# bln-001.net
KiCad netlist of a schematic drawn in EAGLE
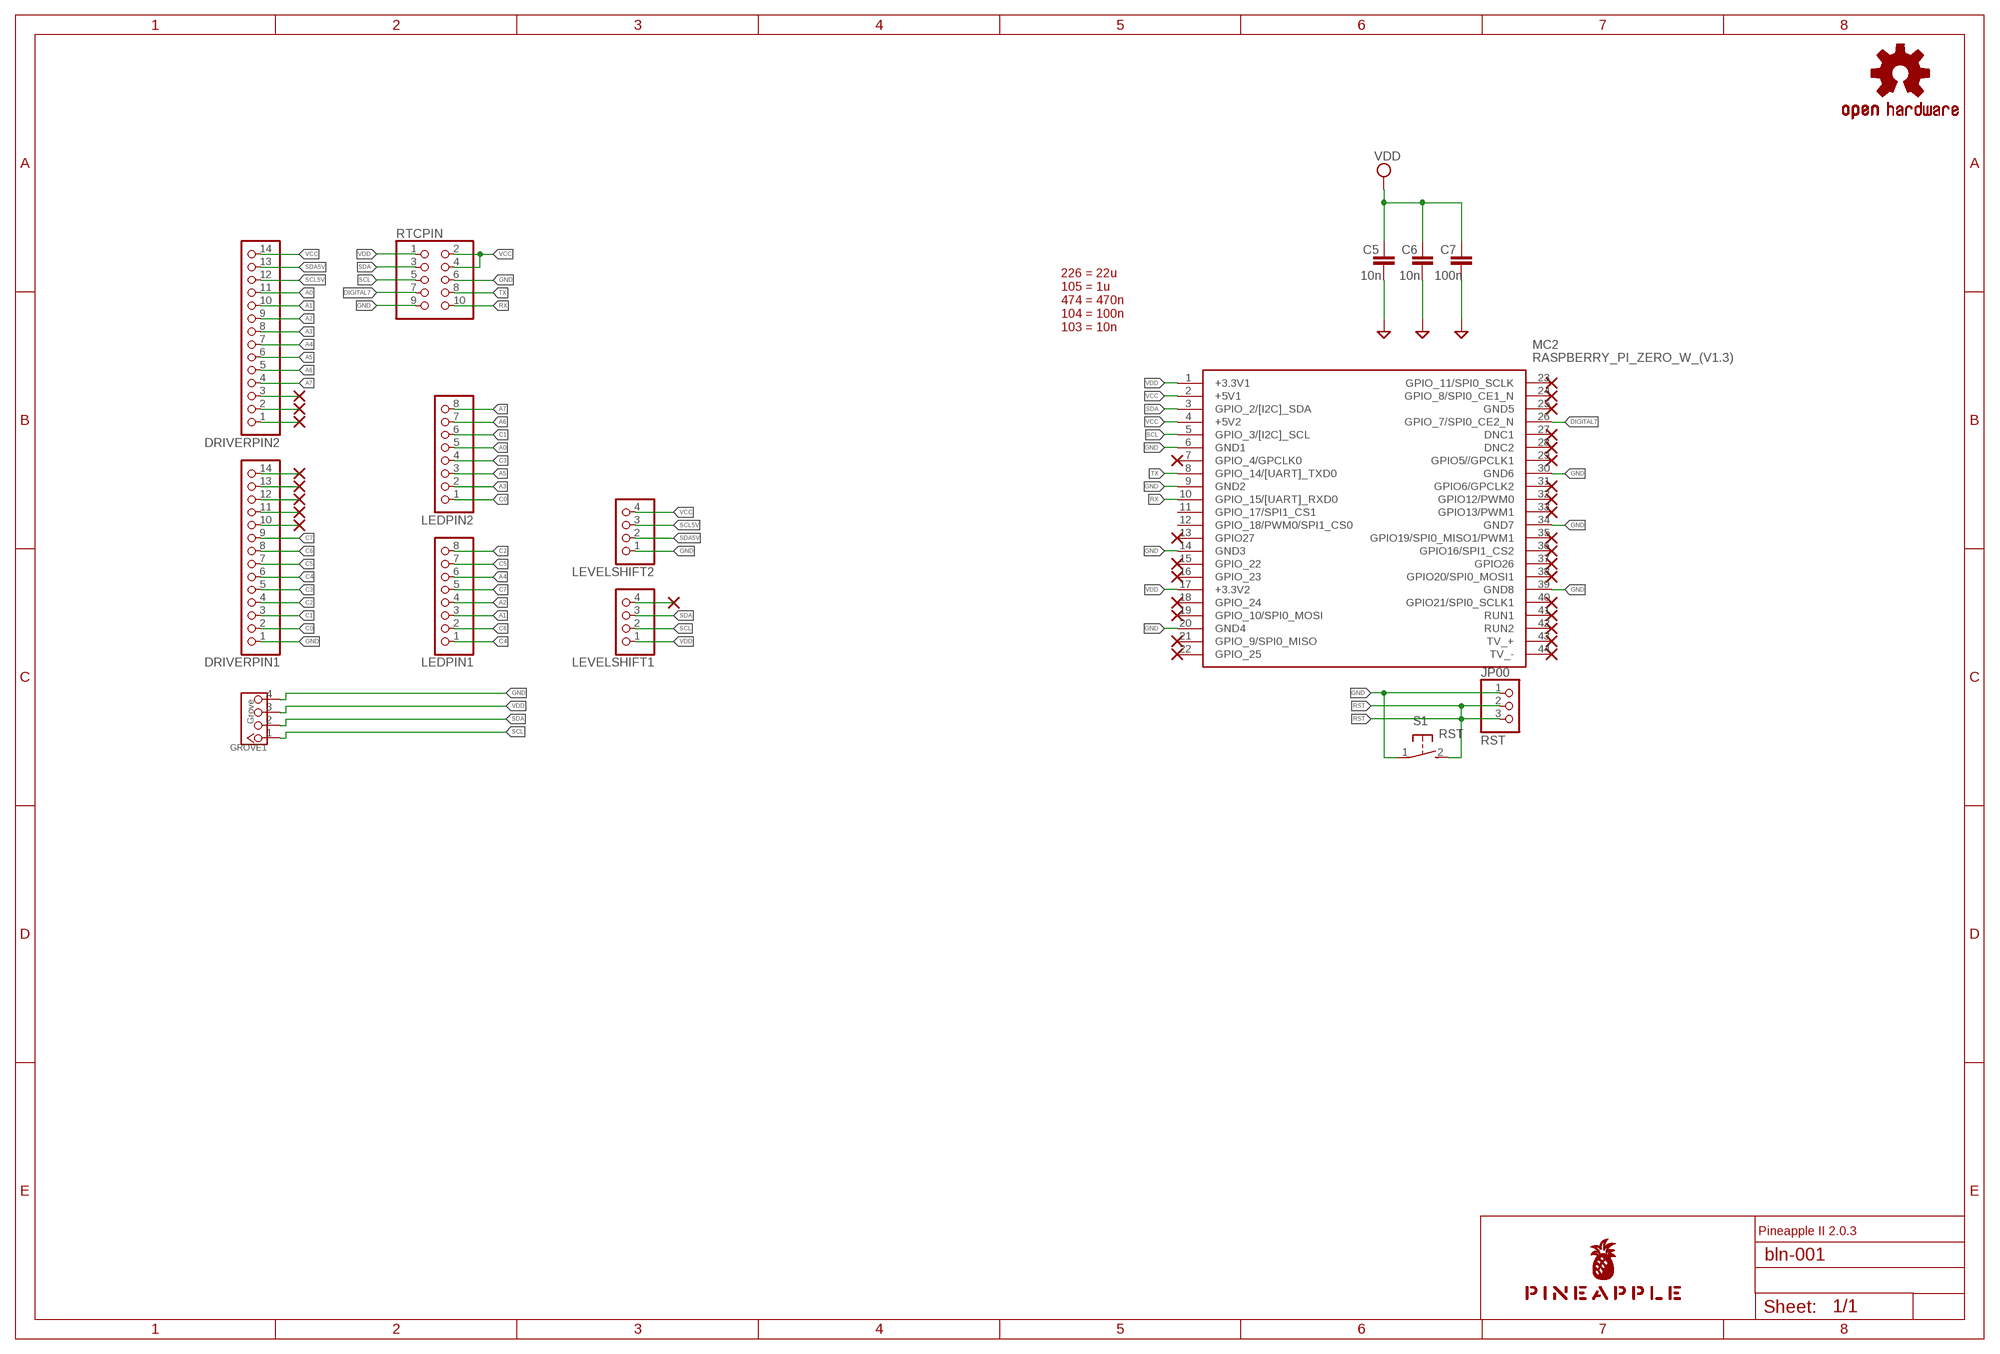
[diagram p0: schematic, sheet 1]

(export (version "E")
  (design (tool "Eeschema 10.0.6"))
  (components
    (comp (ref "C5")
      (value "10n")
      (footprint "eagle-import:C025-024X044")
      (libsource (lib "eagle-import") (part "C-EU025-024X044"))
    )
    (comp (ref "C6")
      (value "10n")
      (footprint "eagle-import:C025-024X044")
      (libsource (lib "eagle-import") (part "C-EU025-024X044"))
    )
    (comp (ref "C7")
      (value "100n")
      (footprint "eagle-import:C025-024X044")
      (libsource (lib "eagle-import") (part "C-EU025-024X044"))
    )
    (comp (ref "DRIVERPIN1")
      (value "PINHD-1X14")
      (footprint "eagle-import:1X14")
      (libsource (lib "eagle-import") (part "PINHD-1X14"))
    )
    (comp (ref "DRIVERPIN2")
      (value "PINHD-1X14")
      (footprint "eagle-import:1X14")
      (libsource (lib "eagle-import") (part "PINHD-1X14"))
    )
    (comp (ref "GROVE1")
      (value "Grove")
      (footprint "eagle-import:4P-2.0-90D")
      (libsource (lib "eagle-import") (part "TWIG-4P-2.0'90D'"))
    )
    (comp (ref "JP00")
      (value "RST")
      (footprint "eagle-import:1X03")
      (libsource (lib "eagle-import") (part "PINHD-1X3"))
    )
    (comp (ref "LEDPIN1")
      (value "PINHD-1X8BIG")
      (footprint "eagle-import:1X08-BIG")
      (libsource (lib "eagle-import") (part "PINHD-1X8BIG"))
    )
    (comp (ref "LEDPIN2")
      (value "PINHD-1X8BIG")
      (footprint "eagle-import:1X08-BIG")
      (libsource (lib "eagle-import") (part "PINHD-1X8BIG"))
    )
    (comp (ref "LEVELSHIFT1")
      (value "PINHD-1X4")
      (footprint "eagle-import:1X04")
      (libsource (lib "eagle-import") (part "PINHD-1X4"))
    )
    (comp (ref "LEVELSHIFT2")
      (value "PINHD-1X4")
      (footprint "eagle-import:1X04")
      (libsource (lib "eagle-import") (part "PINHD-1X4"))
    )
    (comp (ref "LOGO1")
      (value "OSHW-LOGOS-COPPER")
      (footprint "eagle-import:OSHW-LOGO-S_COPPER")
      (libsource (lib "eagle-import") (part "OSHW-LOGOS-COPPER"))
    )
    (comp (ref "MC2")
      (value "RASPBERRY_PI_ZERO_W_(V1.3)")
      (footprint "eagle-import:RASPBERRYPIZEROWV13")
      (fields (field (name "ARROW_PART_NUMBER") "Raspberry Pi Zero W (v1.3)"))
      (libsource (lib "eagle-import") (part "RASPBERRY_PI_ZERO_W_(V1.3)"))
    )
    (comp (ref "RTCPIN")
      (value "PINHD-2X5")
      (footprint "eagle-import:2X05")
      (libsource (lib "eagle-import") (part "PINHD-2X5"))
    )
    (comp (ref "S1")
      (value "RST")
      (footprint "eagle-import:B3F-31XX")
      (fields (field (name "MPN") "B3F-3100"))
      (libsource (lib "eagle-import") (part "31-XX"))
    )
    (comp (ref "U$1")
      (value "PINEAPPLE450_SILK")
      (footprint "eagle-import:PINEAPPLE450_SILK")
      (libsource (lib "eagle-import") (part "PINEAPPLE450_SILK"))
    )
  )
  (nets
    (net (code "1") (name "A0") (class "Default")
      (node (ref "DRIVERPIN2") (pin "11") (pinfunction "11_11") (pintype "passive"))
      (node (ref "LEDPIN2") (pin "5") (pinfunction "5_5") (pintype "passive"))
    )
    (net (code "2") (name "A1") (class "Default")
      (node (ref "DRIVERPIN2") (pin "10") (pinfunction "10_10") (pintype "passive"))
      (node (ref "LEDPIN1") (pin "3") (pinfunction "3_3") (pintype "passive"))
    )
    (net (code "3") (name "A2") (class "Default")
      (node (ref "DRIVERPIN2") (pin "9") (pinfunction "9_9") (pintype "passive"))
      (node (ref "LEDPIN1") (pin "4") (pinfunction "4_4") (pintype "passive"))
    )
    (net (code "4") (name "A3") (class "Default")
      (node (ref "DRIVERPIN2") (pin "8") (pinfunction "8_8") (pintype "passive"))
      (node (ref "LEDPIN2") (pin "2") (pinfunction "2_2") (pintype "passive"))
    )
    (net (code "5") (name "A4") (class "Default")
      (node (ref "DRIVERPIN2") (pin "7") (pinfunction "7_7") (pintype "passive"))
      (node (ref "LEDPIN1") (pin "6") (pinfunction "6_6") (pintype "passive"))
    )
    (net (code "6") (name "A5") (class "Default")
      (node (ref "DRIVERPIN2") (pin "6") (pinfunction "6_6") (pintype "passive"))
      (node (ref "LEDPIN2") (pin "3") (pinfunction "3_3") (pintype "passive"))
    )
    (net (code "7") (name "A6") (class "Default")
      (node (ref "DRIVERPIN2") (pin "5") (pinfunction "5_5") (pintype "passive"))
      (node (ref "LEDPIN2") (pin "7") (pinfunction "7_7") (pintype "passive"))
    )
    (net (code "8") (name "A7") (class "Default")
      (node (ref "DRIVERPIN2") (pin "4") (pinfunction "4_4") (pintype "passive"))
      (node (ref "LEDPIN2") (pin "8") (pinfunction "8_8") (pintype "passive"))
    )
    (net (code "9") (name "C0") (class "Default")
      (node (ref "DRIVERPIN1") (pin "2") (pinfunction "2_2") (pintype "passive"))
      (node (ref "LEDPIN2") (pin "1") (pinfunction "1_1") (pintype "passive"))
    )
    (net (code "10") (name "C1") (class "Default")
      (node (ref "DRIVERPIN1") (pin "3") (pinfunction "3_3") (pintype "passive"))
      (node (ref "LEDPIN2") (pin "6") (pinfunction "6_6") (pintype "passive"))
    )
    (net (code "11") (name "C2") (class "Default")
      (node (ref "DRIVERPIN1") (pin "4") (pinfunction "4_4") (pintype "passive"))
      (node (ref "LEDPIN1") (pin "8") (pinfunction "8_8") (pintype "passive"))
    )
    (net (code "12") (name "C3") (class "Default")
      (node (ref "DRIVERPIN1") (pin "5") (pinfunction "5_5") (pintype "passive"))
      (node (ref "LEDPIN2") (pin "4") (pinfunction "4_4") (pintype "passive"))
    )
    (net (code "13") (name "C4") (class "Default")
      (node (ref "DRIVERPIN1") (pin "6") (pinfunction "6_6") (pintype "passive"))
      (node (ref "LEDPIN1") (pin "1") (pinfunction "1_1") (pintype "passive"))
    )
    (net (code "14") (name "C5") (class "Default")
      (node (ref "DRIVERPIN1") (pin "7") (pinfunction "7_7") (pintype "passive"))
      (node (ref "LEDPIN1") (pin "7") (pinfunction "7_7") (pintype "passive"))
    )
    (net (code "15") (name "C6") (class "Default")
      (node (ref "DRIVERPIN1") (pin "8") (pinfunction "8_8") (pintype "passive"))
      (node (ref "LEDPIN1") (pin "2") (pinfunction "2_2") (pintype "passive"))
    )
    (net (code "16") (name "C7") (class "Default")
      (node (ref "DRIVERPIN1") (pin "9") (pinfunction "9_9") (pintype "passive"))
      (node (ref "LEDPIN1") (pin "5") (pinfunction "5_5") (pintype "passive"))
    )
    (net (code "17") (name "DIGITAL7") (class "Default")
      (node (ref "MC2") (pin "26") (pinfunction "GPIO_7/SPI0_CE2_N_26") (pintype "bidirectional"))
      (node (ref "RTCPIN") (pin "7") (pinfunction "7_7") (pintype "passive"))
    )
    (net (code "18") (name "GND") (class "Default")
      (node (ref "C5") (pin "2") (pinfunction "2_2") (pintype "passive"))
      (node (ref "C6") (pin "2") (pinfunction "2_2") (pintype "passive"))
      (node (ref "C7") (pin "2") (pinfunction "2_2") (pintype "passive"))
      (node (ref "DRIVERPIN1") (pin "1") (pinfunction "1_1") (pintype "passive"))
      (node (ref "GROVE1") (pin "4") (pinfunction "4_4") (pintype "bidirectional"))
      (node (ref "JP00") (pin "1") (pinfunction "1_1") (pintype "passive"))
      (node (ref "LEVELSHIFT2") (pin "1") (pinfunction "1_1") (pintype "passive"))
      (node (ref "MC2") (pin "14") (pinfunction "GND3_14") (pintype "bidirectional"))
      (node (ref "MC2") (pin "20") (pinfunction "GND4_20") (pintype "bidirectional"))
      (node (ref "MC2") (pin "30") (pinfunction "GND6_30") (pintype "bidirectional"))
      (node (ref "MC2") (pin "34") (pinfunction "GND7_34") (pintype "bidirectional"))
      (node (ref "MC2") (pin "39") (pinfunction "GND8_39") (pintype "bidirectional"))
      (node (ref "MC2") (pin "6") (pinfunction "GND1_6") (pintype "bidirectional"))
      (node (ref "MC2") (pin "9") (pinfunction "GND2_9") (pintype "bidirectional"))
      (node (ref "RTCPIN") (pin "6") (pinfunction "6_6") (pintype "passive"))
      (node (ref "RTCPIN") (pin "9") (pinfunction "9_9") (pintype "passive"))
      (node (ref "S1") (pin "1") (pinfunction "P_1") (pintype "passive"))
    )
    (net (code "19") (name "RST") (class "Default")
      (node (ref "JP00") (pin "2") (pinfunction "2_2") (pintype "passive"))
      (node (ref "JP00") (pin "3") (pinfunction "3_3") (pintype "passive"))
      (node (ref "S1") (pin "2") (pinfunction "S_2") (pintype "passive"))
    )
    (net (code "20") (name "RX") (class "Default")
      (node (ref "MC2") (pin "10") (pinfunction "GPIO_15/[UART]_RXD0_10") (pintype "bidirectional"))
      (node (ref "RTCPIN") (pin "10") (pinfunction "10_10") (pintype "passive"))
    )
    (net (code "21") (name "SCL") (class "Default")
      (node (ref "GROVE1") (pin "1") (pinfunction "1_1") (pintype "bidirectional"))
      (node (ref "LEVELSHIFT1") (pin "2") (pinfunction "2_2") (pintype "passive"))
      (node (ref "MC2") (pin "5") (pinfunction "GPIO_3/[I2C]_SCL_5") (pintype "bidirectional"))
      (node (ref "RTCPIN") (pin "5") (pinfunction "5_5") (pintype "passive"))
    )
    (net (code "22") (name "SCL5V") (class "Default")
      (node (ref "DRIVERPIN2") (pin "12") (pinfunction "12_12") (pintype "passive"))
      (node (ref "LEVELSHIFT2") (pin "3") (pinfunction "3_3") (pintype "passive"))
    )
    (net (code "23") (name "SDA") (class "Default")
      (node (ref "GROVE1") (pin "2") (pinfunction "2_2") (pintype "bidirectional"))
      (node (ref "LEVELSHIFT1") (pin "3") (pinfunction "3_3") (pintype "passive"))
      (node (ref "MC2") (pin "3") (pinfunction "GPIO_2/[I2C]_SDA_3") (pintype "bidirectional"))
      (node (ref "RTCPIN") (pin "3") (pinfunction "3_3") (pintype "passive"))
    )
    (net (code "24") (name "SDA5V") (class "Default")
      (node (ref "DRIVERPIN2") (pin "13") (pinfunction "13_13") (pintype "passive"))
      (node (ref "LEVELSHIFT2") (pin "2") (pinfunction "2_2") (pintype "passive"))
    )
    (net (code "25") (name "TX") (class "Default")
      (node (ref "MC2") (pin "8") (pinfunction "GPIO_14/[UART]_TXD0_8") (pintype "bidirectional"))
      (node (ref "RTCPIN") (pin "8") (pinfunction "8_8") (pintype "passive"))
    )
    (net (code "26") (name "VCC") (class "Default")
      (node (ref "DRIVERPIN2") (pin "14") (pinfunction "14_14") (pintype "passive"))
      (node (ref "LEVELSHIFT2") (pin "4") (pinfunction "4_4") (pintype "passive"))
      (node (ref "MC2") (pin "2") (pinfunction "+5V1_2") (pintype "bidirectional"))
      (node (ref "MC2") (pin "4") (pinfunction "+5V2_4") (pintype "bidirectional"))
      (node (ref "RTCPIN") (pin "2") (pinfunction "2_2") (pintype "passive"))
      (node (ref "RTCPIN") (pin "4") (pinfunction "4_4") (pintype "passive"))
    )
    (net (code "27") (name "VDD") (class "Default")
      (node (ref "C5") (pin "1") (pinfunction "1_1") (pintype "passive"))
      (node (ref "C6") (pin "1") (pinfunction "1_1") (pintype "passive"))
      (node (ref "C7") (pin "1") (pinfunction "1_1") (pintype "passive"))
      (node (ref "GROVE1") (pin "3") (pinfunction "3_3") (pintype "bidirectional"))
      (node (ref "LEVELSHIFT1") (pin "1") (pinfunction "1_1") (pintype "passive"))
      (node (ref "MC2") (pin "1") (pinfunction "+3.3V1_1") (pintype "bidirectional"))
      (node (ref "MC2") (pin "17") (pinfunction "+3.3V2_17") (pintype "bidirectional"))
      (node (ref "RTCPIN") (pin "1") (pinfunction "1_1") (pintype "passive"))
    )
    (net (code "28") (name "unconnected-(DRIVERPIN1-Pad10)") (class "Default")
      (node (ref "DRIVERPIN1") (pin "10") (pinfunction "10_10") (pintype "passive"))
    )
    (net (code "29") (name "unconnected-(DRIVERPIN1-Pad11)") (class "Default")
      (node (ref "DRIVERPIN1") (pin "11") (pinfunction "11_11") (pintype "passive"))
    )
    (net (code "30") (name "unconnected-(DRIVERPIN1-Pad12)") (class "Default")
      (node (ref "DRIVERPIN1") (pin "12") (pinfunction "12_12") (pintype "passive"))
    )
    (net (code "31") (name "unconnected-(DRIVERPIN1-Pad13)") (class "Default")
      (node (ref "DRIVERPIN1") (pin "13") (pinfunction "13_13") (pintype "passive"))
    )
    (net (code "32") (name "unconnected-(DRIVERPIN1-Pad14)") (class "Default")
      (node (ref "DRIVERPIN1") (pin "14") (pinfunction "14_14") (pintype "passive"))
    )
    (net (code "33") (name "unconnected-(DRIVERPIN2-Pad1)") (class "Default")
      (node (ref "DRIVERPIN2") (pin "1") (pinfunction "1_1") (pintype "passive"))
    )
    (net (code "34") (name "unconnected-(DRIVERPIN2-Pad2)") (class "Default")
      (node (ref "DRIVERPIN2") (pin "2") (pinfunction "2_2") (pintype "passive"))
    )
    (net (code "35") (name "unconnected-(DRIVERPIN2-Pad3)") (class "Default")
      (node (ref "DRIVERPIN2") (pin "3") (pinfunction "3_3") (pintype "passive"))
    )
    (net (code "36") (name "unconnected-(LEVELSHIFT1-Pad4)") (class "Default")
      (node (ref "LEVELSHIFT1") (pin "4") (pinfunction "4_4") (pintype "passive"))
    )
    (net (code "37") (name "unconnected-(MC2-DNC1-Pad27)") (class "Default")
      (node (ref "MC2") (pin "27") (pinfunction "DNC1_27") (pintype "bidirectional"))
    )
    (net (code "38") (name "unconnected-(MC2-DNC2-Pad28)") (class "Default")
      (node (ref "MC2") (pin "28") (pinfunction "DNC2_28") (pintype "bidirectional"))
    )
    (net (code "39") (name "unconnected-(MC2-GND5-Pad25)") (class "Default")
      (node (ref "MC2") (pin "25") (pinfunction "GND5_25") (pintype "bidirectional"))
    )
    (net (code "40") (name "unconnected-(MC2-GPIO5{slash}{slash}GPCLK1-Pad29)") (class "Default")
      (node (ref "MC2") (pin "29") (pinfunction "GPIO5//GPCLK1_29") (pintype "bidirectional"))
    )
    (net (code "41") (name "unconnected-(MC2-GPIO6{slash}GPCLK2-Pad31)") (class "Default")
      (node (ref "MC2") (pin "31") (pinfunction "GPIO6/GPCLK2_31") (pintype "bidirectional"))
    )
    (net (code "42") (name "unconnected-(MC2-GPIO12{slash}PWM0-Pad32)") (class "Default")
      (node (ref "MC2") (pin "32") (pinfunction "GPIO12/PWM0_32") (pintype "bidirectional"))
    )
    (net (code "43") (name "unconnected-(MC2-GPIO13{slash}PWM1-Pad33)") (class "Default")
      (node (ref "MC2") (pin "33") (pinfunction "GPIO13/PWM1_33") (pintype "bidirectional"))
    )
    (net (code "44") (name "unconnected-(MC2-GPIO16{slash}SPI1_CS2-Pad36)") (class "Default")
      (node (ref "MC2") (pin "36") (pinfunction "GPIO16/SPI1_CS2_36") (pintype "bidirectional"))
    )
    (net (code "45") (name "unconnected-(MC2-GPIO19{slash}SPI0_MISO1{slash}PWM1-Pad35)") (class "Default")
      (node (ref "MC2") (pin "35") (pinfunction "GPIO19/SPI0_MISO1/PWM1_35") (pintype "bidirectional"))
    )
    (net (code "46") (name "unconnected-(MC2-GPIO20{slash}SPI0_MOSI1-Pad38)") (class "Default")
      (node (ref "MC2") (pin "38") (pinfunction "GPIO20/SPI0_MOSI1_38") (pintype "bidirectional"))
    )
    (net (code "47") (name "unconnected-(MC2-GPIO21{slash}SPI0_SCLK1-Pad40)") (class "Default")
      (node (ref "MC2") (pin "40") (pinfunction "GPIO21/SPI0_SCLK1_40") (pintype "bidirectional"))
    )
    (net (code "48") (name "unconnected-(MC2-GPIO26-Pad37)") (class "Default")
      (node (ref "MC2") (pin "37") (pinfunction "GPIO26_37") (pintype "bidirectional"))
    )
    (net (code "49") (name "unconnected-(MC2-GPIO27-Pad13)") (class "Default")
      (node (ref "MC2") (pin "13") (pinfunction "GPIO27_13") (pintype "bidirectional"))
    )
    (net (code "50") (name "unconnected-(MC2-GPIO_4{slash}GPCLK0-Pad7)") (class "Default")
      (node (ref "MC2") (pin "7") (pinfunction "GPIO_4/GPCLK0_7") (pintype "bidirectional"))
    )
    (net (code "51") (name "unconnected-(MC2-GPIO_8{slash}SPI0_CE1_N-Pad24)") (class "Default")
      (node (ref "MC2") (pin "24") (pinfunction "GPIO_8/SPI0_CE1_N_24") (pintype "bidirectional"))
    )
    (net (code "52") (name "unconnected-(MC2-GPIO_9{slash}SPI0_MISO-Pad21)") (class "Default")
      (node (ref "MC2") (pin "21") (pinfunction "GPIO_9/SPI0_MISO_21") (pintype "bidirectional"))
    )
    (net (code "53") (name "unconnected-(MC2-GPIO_10{slash}SPI0_MOSI-Pad19)") (class "Default")
      (node (ref "MC2") (pin "19") (pinfunction "GPIO_10/SPI0_MOSI_19") (pintype "bidirectional"))
    )
    (net (code "54") (name "unconnected-(MC2-GPIO_11{slash}SPI0_SCLK-Pad23)") (class "Default")
      (node (ref "MC2") (pin "23") (pinfunction "GPIO_11/SPI0_SCLK_23") (pintype "bidirectional"))
    )
    (net (code "55") (name "unconnected-(MC2-GPIO_17{slash}SPI1_CS1-Pad11)") (class "Default")
      (node (ref "MC2") (pin "11") (pinfunction "GPIO_17/SPI1_CS1_11") (pintype "bidirectional"))
    )
    (net (code "56") (name "unconnected-(MC2-GPIO_18{slash}PWM0{slash}SPI1_CS0-Pad12)") (class "Default")
      (node (ref "MC2") (pin "12") (pinfunction "GPIO_18/PWM0/SPI1_CS0_12") (pintype "bidirectional"))
    )
    (net (code "57") (name "unconnected-(MC2-GPIO_22-Pad15)") (class "Default")
      (node (ref "MC2") (pin "15") (pinfunction "GPIO_22_15") (pintype "bidirectional"))
    )
    (net (code "58") (name "unconnected-(MC2-GPIO_23-Pad16)") (class "Default")
      (node (ref "MC2") (pin "16") (pinfunction "GPIO_23_16") (pintype "bidirectional"))
    )
    (net (code "59") (name "unconnected-(MC2-GPIO_24-Pad18)") (class "Default")
      (node (ref "MC2") (pin "18") (pinfunction "GPIO_24_18") (pintype "bidirectional"))
    )
    (net (code "60") (name "unconnected-(MC2-GPIO_25-Pad22)") (class "Default")
      (node (ref "MC2") (pin "22") (pinfunction "GPIO_25_22") (pintype "bidirectional"))
    )
    (net (code "61") (name "unconnected-(MC2-RUN1-Pad41)") (class "Default")
      (node (ref "MC2") (pin "41") (pinfunction "RUN1_41") (pintype "bidirectional"))
    )
    (net (code "62") (name "unconnected-(MC2-RUN2-Pad42)") (class "Default")
      (node (ref "MC2") (pin "42") (pinfunction "RUN2_42") (pintype "bidirectional"))
    )
    (net (code "63") (name "unconnected-(MC2-TV_+-Pad43)") (class "Default")
      (node (ref "MC2") (pin "43") (pinfunction "TV_+_43") (pintype "bidirectional"))
    )
    (net (code "64") (name "unconnected-(MC2-TV_--Pad44)") (class "Default")
      (node (ref "MC2") (pin "44") (pinfunction "TV_-_44") (pintype "bidirectional"))
    )
  )
)
